# EchoReverbUnit.net
KiCad netlist of a schematic drawn in EAGLE
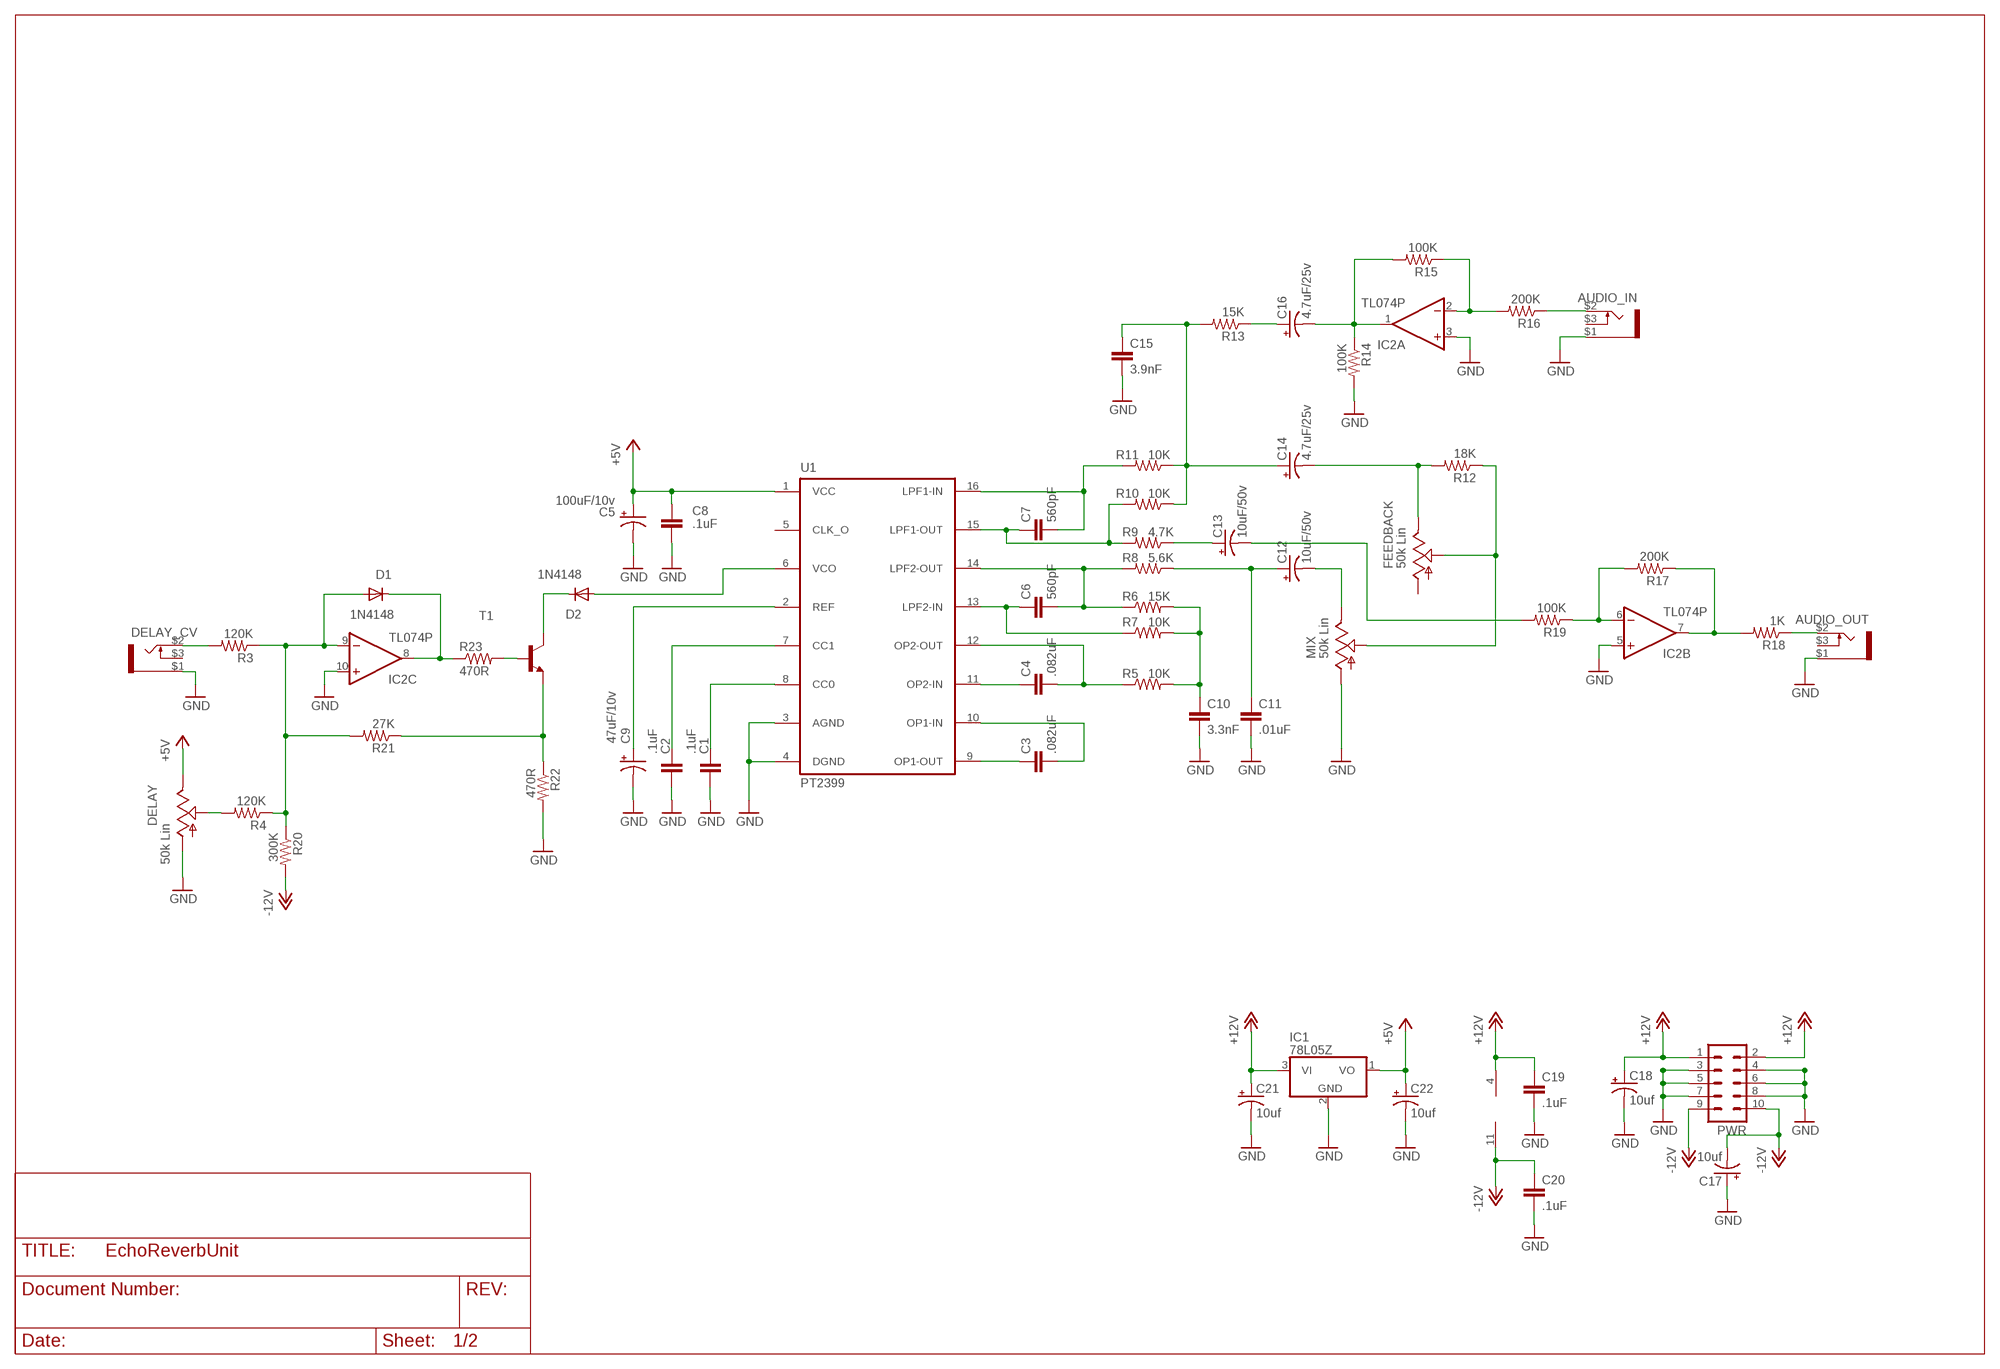
[diagram p0: schematic, sheet 1]

(export (version "E")
  (design (tool "Eeschema 10.0.6"))
  (components
    (comp (ref "AUDIO_IN")
      (value "PJ-323PJ-323")
      (footprint "eagle-import:PJ-323")
      (libsource (lib "eagle-import") (part "PJ-323PJ-323"))
    )
    (comp (ref "AUDIO_OUT")
      (value "PJ-323PJ-323")
      (footprint "eagle-import:PJ-323")
      (libsource (lib "eagle-import") (part "PJ-323PJ-323"))
    )
    (comp (ref "C1")
      (value ".1uF")
      (footprint "eagle-import:C050-024X044")
      (libsource (lib "eagle-import") (part "C-EU050-024X044"))
    )
    (comp (ref "C2")
      (value ".1uF")
      (footprint "eagle-import:C050-024X044")
      (libsource (lib "eagle-import") (part "C-EU050-024X044"))
    )
    (comp (ref "C3")
      (value ".082uF")
      (footprint "eagle-import:C050-024X044")
      (libsource (lib "eagle-import") (part "C-EU050-024X044"))
    )
    (comp (ref "C4")
      (value ".082uF")
      (footprint "eagle-import:C050-024X044")
      (libsource (lib "eagle-import") (part "C-EU050-024X044"))
    )
    (comp (ref "C5")
      (value "100uF/10v")
      (footprint "eagle-import:E2,5-6")
      (libsource (lib "eagle-import") (part "CPOL-USE2.5-6"))
    )
    (comp (ref "C6")
      (value "560pF")
      (footprint "eagle-import:C050-024X044")
      (libsource (lib "eagle-import") (part "C-EU050-024X044"))
    )
    (comp (ref "C7")
      (value "560pF")
      (footprint "eagle-import:C050-024X044")
      (libsource (lib "eagle-import") (part "C-EU050-024X044"))
    )
    (comp (ref "C8")
      (value ".1uF")
      (footprint "eagle-import:C050-024X044")
      (libsource (lib "eagle-import") (part "C-EU050-024X044"))
    )
    (comp (ref "C9")
      (value "47uF/10v")
      (footprint "eagle-import:E2,5-6")
      (libsource (lib "eagle-import") (part "CPOL-USE2.5-6"))
    )
    (comp (ref "C10")
      (value "3.3nF")
      (footprint "eagle-import:C050-024X044")
      (libsource (lib "eagle-import") (part "C-EU050-024X044"))
    )
    (comp (ref "C11")
      (value ".01uF")
      (footprint "eagle-import:C050-024X044")
      (libsource (lib "eagle-import") (part "C-EU050-024X044"))
    )
    (comp (ref "C12")
      (value "10uF/50v")
      (footprint "eagle-import:E2,5-6")
      (libsource (lib "eagle-import") (part "CPOL-USE2.5-6"))
    )
    (comp (ref "C13")
      (value "10uF/50v")
      (footprint "eagle-import:E2,5-6")
      (libsource (lib "eagle-import") (part "CPOL-USE2.5-6"))
    )
    (comp (ref "C14")
      (value "4.7uF/25v")
      (footprint "eagle-import:E2,5-6")
      (libsource (lib "eagle-import") (part "CPOL-USE2.5-6"))
    )
    (comp (ref "C15")
      (value "3.9nF")
      (footprint "eagle-import:C050-024X044")
      (libsource (lib "eagle-import") (part "C-EU050-024X044"))
    )
    (comp (ref "C16")
      (value "4.7uF/25v")
      (footprint "eagle-import:E2,5-6")
      (libsource (lib "eagle-import") (part "CPOL-USE2.5-6"))
    )
    (comp (ref "C17")
      (value "10uf")
      (footprint "eagle-import:E2,5-5")
      (libsource (lib "eagle-import") (part "CPOL-USE2.5-5"))
    )
    (comp (ref "C18")
      (value "10uf")
      (footprint "eagle-import:E2,5-5")
      (libsource (lib "eagle-import") (part "CPOL-USE2.5-5"))
    )
    (comp (ref "C19")
      (value ".1uF")
      (footprint "eagle-import:C050-024X044")
      (libsource (lib "eagle-import") (part "C-EU050-024X044"))
    )
    (comp (ref "C20")
      (value ".1uF")
      (footprint "eagle-import:C050-024X044")
      (libsource (lib "eagle-import") (part "C-EU050-024X044"))
    )
    (comp (ref "C21")
      (value "10uf")
      (footprint "eagle-import:E2,5-5")
      (libsource (lib "eagle-import") (part "CPOL-USE2.5-5"))
    )
    (comp (ref "C22")
      (value "10uf")
      (footprint "eagle-import:E2,5-5")
      (libsource (lib "eagle-import") (part "CPOL-USE2.5-5"))
    )
    (comp (ref "D1")
      (value "1N4148")
      (footprint "eagle-import:DO35-7")
      (libsource (lib "eagle-import") (part "1N4148DO35-7"))
    )
    (comp (ref "D2")
      (value "1N4148")
      (footprint "eagle-import:DO35-7")
      (libsource (lib "eagle-import") (part "1N4148DO35-7"))
    )
    (comp (ref "DELAY")
      (value "50k Lin")
      (footprint "eagle-import:EVUF")
      (libsource (lib "eagle-import") (part "RIGHT-ANGLE-POTA"))
    )
    (comp (ref "DELAY_CV")
      (value "PJ-323PJ-323")
      (footprint "eagle-import:PJ-323")
      (libsource (lib "eagle-import") (part "PJ-323PJ-323"))
    )
    (comp (ref "FEEDBACK")
      (value "50k Lin")
      (footprint "eagle-import:EVUF")
      (libsource (lib "eagle-import") (part "RIGHT-ANGLE-POTA"))
    )
    (comp (ref "IC1")
      (value "78L05Z")
      (footprint "eagle-import:TO92")
      (libsource (lib "eagle-import") (part "78ZL05"))
    )
    (comp (ref "IC2")
      (value "TL074P")
      (footprint "eagle-import:DIL14")
      (libsource (lib "eagle-import") (part "TL074P"))
    )
    (comp (ref "MIX")
      (value "50k Lin")
      (footprint "eagle-import:EVUF")
      (libsource (lib "eagle-import") (part "RIGHT-ANGLE-POTA"))
    )
    (comp (ref "PWR")
      (value "ML10")
      (footprint "eagle-import:ML10")
      (libsource (lib "eagle-import") (part "ML10"))
    )
    (comp (ref "R3")
      (value "120K")
      (footprint "eagle-import:0207_7")
      (libsource (lib "eagle-import") (part "R-US_0207/7"))
    )
    (comp (ref "R4")
      (value "120K")
      (footprint "eagle-import:0207_7")
      (libsource (lib "eagle-import") (part "R-US_0207/7"))
    )
    (comp (ref "R5")
      (value "10K")
      (footprint "eagle-import:0207_7")
      (libsource (lib "eagle-import") (part "R-US_0207/7"))
    )
    (comp (ref "R6")
      (value "15K")
      (footprint "eagle-import:0207_7")
      (libsource (lib "eagle-import") (part "R-US_0207/7"))
    )
    (comp (ref "R7")
      (value "10K")
      (footprint "eagle-import:0207_7")
      (libsource (lib "eagle-import") (part "R-US_0207/7"))
    )
    (comp (ref "R8")
      (value "5.6K")
      (footprint "eagle-import:0207_7")
      (libsource (lib "eagle-import") (part "R-US_0207/7"))
    )
    (comp (ref "R9")
      (value "4.7K")
      (footprint "eagle-import:0207_7")
      (libsource (lib "eagle-import") (part "R-US_0207/7"))
    )
    (comp (ref "R10")
      (value "10K")
      (footprint "eagle-import:0207_7")
      (libsource (lib "eagle-import") (part "R-US_0207/7"))
    )
    (comp (ref "R11")
      (value "10K")
      (footprint "eagle-import:0207_7")
      (libsource (lib "eagle-import") (part "R-US_0207/7"))
    )
    (comp (ref "R12")
      (value "18K")
      (footprint "eagle-import:0207_7")
      (libsource (lib "eagle-import") (part "R-US_0207/7"))
    )
    (comp (ref "R13")
      (value "15K")
      (footprint "eagle-import:0207_7")
      (libsource (lib "eagle-import") (part "R-US_0207/7"))
    )
    (comp (ref "R14")
      (value "100K")
      (footprint "eagle-import:0207_7")
      (libsource (lib "eagle-import") (part "R-US_0207/7"))
    )
    (comp (ref "R15")
      (value "100K")
      (footprint "eagle-import:0207_7")
      (libsource (lib "eagle-import") (part "R-US_0207/7"))
    )
    (comp (ref "R16")
      (value "200K")
      (footprint "eagle-import:0207_7")
      (libsource (lib "eagle-import") (part "R-US_0207/7"))
    )
    (comp (ref "R17")
      (value "200K")
      (footprint "eagle-import:0207_7")
      (libsource (lib "eagle-import") (part "R-US_0207/7"))
    )
    (comp (ref "R18")
      (value "1K")
      (footprint "eagle-import:0207_7")
      (libsource (lib "eagle-import") (part "R-US_0207/7"))
    )
    (comp (ref "R19")
      (value "100K")
      (footprint "eagle-import:0207_7")
      (libsource (lib "eagle-import") (part "R-US_0207/7"))
    )
    (comp (ref "R20")
      (value "300K")
      (footprint "eagle-import:0207_7")
      (libsource (lib "eagle-import") (part "R-US_0207/7"))
    )
    (comp (ref "R21")
      (value "27K")
      (footprint "eagle-import:0207_7")
      (libsource (lib "eagle-import") (part "R-US_0207/7"))
    )
    (comp (ref "R22")
      (value "470R")
      (footprint "eagle-import:0207_7")
      (libsource (lib "eagle-import") (part "R-US_0207/7"))
    )
    (comp (ref "R23")
      (value "470R")
      (footprint "eagle-import:0207_7")
      (libsource (lib "eagle-import") (part "R-US_0207/7"))
    )
    (comp (ref "T1")
      (value "2N3904-NPN-TO92-EBC")
      (footprint "eagle-import:TO92-EBC")
      (libsource (lib "eagle-import") (part "-NPN-TO92-EBC2N3904"))
    )
    (comp (ref "U1")
      (value "PT2399")
      (footprint "eagle-import:DIL16")
      (fields (field (name "MF") "AC Delco"))
      (libsource (lib "eagle-import") (part "PT2399"))
    )
  )
  (nets
    (net (code "1") (name "+5V") (class "Default")
      (node (ref "C22") (pin "+") (pinfunction "+_+") (pintype "passive"))
      (node (ref "C5") (pin "+") (pinfunction "+_+") (pintype "passive"))
      (node (ref "C8") (pin "1") (pinfunction "1_1") (pintype "passive"))
      (node (ref "DELAY") (pin "3") (pinfunction "E_3") (pintype "passive"))
      (node (ref "IC1") (pin "1") (pinfunction "VO_1") (pintype "passive"))
      (node (ref "U1") (pin "1") (pinfunction "VCC_1") (pintype "power_in"))
    )
    (net (code "2") (name "+12V") (class "Default")
      (node (ref "C18") (pin "+") (pinfunction "+_+") (pintype "passive"))
      (node (ref "C19") (pin "1") (pinfunction "1_1") (pintype "passive"))
      (node (ref "C21") (pin "+") (pinfunction "+_+") (pintype "passive"))
      (node (ref "IC1") (pin "3") (pinfunction "VI_3") (pintype "input"))
      (node (ref "IC2") (pin "4") (pinfunction "V+_4") (pintype "power_in"))
      (node (ref "PWR") (pin "1") (pinfunction "1_1") (pintype "passive"))
      (node (ref "PWR") (pin "2") (pinfunction "2_2") (pintype "passive"))
    )
    (net (code "3") (name "-12V") (class "Default")
      (node (ref "C17") (pin "-") (pinfunction "-_-") (pintype "passive"))
      (node (ref "C20") (pin "1") (pinfunction "1_1") (pintype "passive"))
      (node (ref "IC2") (pin "11") (pinfunction "V-_11") (pintype "power_in"))
      (node (ref "PWR") (pin "10") (pinfunction "10_10") (pintype "passive"))
      (node (ref "PWR") (pin "9") (pinfunction "9_9") (pintype "passive"))
      (node (ref "R20") (pin "2") (pinfunction "2_2") (pintype "passive"))
    )
    (net (code "4") (name "GND") (class "Default")
      (node (ref "AUDIO_IN") (pin "$1") (pinfunction "3_$1") (pintype "passive"))
      (node (ref "AUDIO_OUT") (pin "$1") (pinfunction "3_$1") (pintype "passive"))
      (node (ref "C1") (pin "2") (pinfunction "2_2") (pintype "passive"))
      (node (ref "C10") (pin "2") (pinfunction "2_2") (pintype "passive"))
      (node (ref "C11") (pin "2") (pinfunction "2_2") (pintype "passive"))
      (node (ref "C15") (pin "2") (pinfunction "2_2") (pintype "passive"))
      (node (ref "C17") (pin "+") (pinfunction "+_+") (pintype "passive"))
      (node (ref "C18") (pin "-") (pinfunction "-_-") (pintype "passive"))
      (node (ref "C19") (pin "2") (pinfunction "2_2") (pintype "passive"))
      (node (ref "C2") (pin "2") (pinfunction "2_2") (pintype "passive"))
      (node (ref "C20") (pin "2") (pinfunction "2_2") (pintype "passive"))
      (node (ref "C21") (pin "-") (pinfunction "-_-") (pintype "passive"))
      (node (ref "C22") (pin "-") (pinfunction "-_-") (pintype "passive"))
      (node (ref "C5") (pin "-") (pinfunction "-_-") (pintype "passive"))
      (node (ref "C8") (pin "2") (pinfunction "2_2") (pintype "passive"))
      (node (ref "C9") (pin "-") (pinfunction "-_-") (pintype "passive"))
      (node (ref "DELAY") (pin "1") (pinfunction "A_1") (pintype "passive"))
      (node (ref "DELAY_CV") (pin "$1") (pinfunction "3_$1") (pintype "passive"))
      (node (ref "IC1") (pin "2") (pinfunction "GND_2") (pintype "passive"))
      (node (ref "IC2") (pin "10") (pinfunction "+IN_10") (pintype "input"))
      (node (ref "IC2") (pin "3") (pinfunction "+IN_3") (pintype "input"))
      (node (ref "IC2") (pin "5") (pinfunction "+IN_5") (pintype "input"))
      (node (ref "MIX") (pin "1") (pinfunction "A_1") (pintype "passive"))
      (node (ref "PWR") (pin "3") (pinfunction "3_3") (pintype "passive"))
      (node (ref "PWR") (pin "4") (pinfunction "4_4") (pintype "passive"))
      (node (ref "PWR") (pin "5") (pinfunction "5_5") (pintype "passive"))
      (node (ref "PWR") (pin "6") (pinfunction "6_6") (pintype "passive"))
      (node (ref "PWR") (pin "7") (pinfunction "7_7") (pintype "passive"))
      (node (ref "PWR") (pin "8") (pinfunction "8_8") (pintype "passive"))
      (node (ref "R14") (pin "2") (pinfunction "2_2") (pintype "passive"))
      (node (ref "R22") (pin "2") (pinfunction "2_2") (pintype "passive"))
      (node (ref "U1") (pin "3") (pinfunction "AGND_3") (pintype "power_in"))
      (node (ref "U1") (pin "4") (pinfunction "DGND_4") (pintype "power_in"))
    )
    (net (code "5") (name "Net-(AUDIO_IN-1)") (class "Default")
      (node (ref "AUDIO_IN") (pin "$2") (pinfunction "1_$2") (pintype "passive"))
      (node (ref "R16") (pin "1") (pinfunction "1_1") (pintype "passive"))
    )
    (net (code "6") (name "Net-(AUDIO_OUT-1)") (class "Default")
      (node (ref "AUDIO_OUT") (pin "$2") (pinfunction "1_$2") (pintype "passive"))
      (node (ref "R18") (pin "1") (pinfunction "1_1") (pintype "passive"))
    )
    (net (code "7") (name "Net-(C10-Pad1)") (class "Default")
      (node (ref "C10") (pin "1") (pinfunction "1_1") (pintype "passive"))
      (node (ref "R5") (pin "2") (pinfunction "2_2") (pintype "passive"))
      (node (ref "R6") (pin "2") (pinfunction "2_2") (pintype "passive"))
      (node (ref "R7") (pin "2") (pinfunction "2_2") (pintype "passive"))
    )
    (net (code "8") (name "Net-(C11-Pad1)") (class "Default")
      (node (ref "C11") (pin "1") (pinfunction "1_1") (pintype "passive"))
      (node (ref "C12") (pin "+") (pinfunction "+_+") (pintype "passive"))
      (node (ref "R8") (pin "1") (pinfunction "1_1") (pintype "passive"))
    )
    (net (code "9") (name "Net-(C13-Pad+)") (class "Default")
      (node (ref "C13") (pin "+") (pinfunction "+_+") (pintype "passive"))
      (node (ref "R9") (pin "1") (pinfunction "1_1") (pintype "passive"))
    )
    (net (code "10") (name "Net-(C13-Pad-)") (class "Default")
      (node (ref "C13") (pin "-") (pinfunction "-_-") (pintype "passive"))
      (node (ref "R19") (pin "2") (pinfunction "2_2") (pintype "passive"))
    )
    (net (code "11") (name "Net-(C14-Pad+)") (class "Default")
      (node (ref "C14") (pin "+") (pinfunction "+_+") (pintype "passive"))
      (node (ref "C15") (pin "1") (pinfunction "1_1") (pintype "passive"))
      (node (ref "R10") (pin "1") (pinfunction "1_1") (pintype "passive"))
      (node (ref "R11") (pin "1") (pinfunction "1_1") (pintype "passive"))
      (node (ref "R13") (pin "2") (pinfunction "2_2") (pintype "passive"))
    )
    (net (code "12") (name "Net-(C16-Pad+)") (class "Default")
      (node (ref "C16") (pin "+") (pinfunction "+_+") (pintype "passive"))
      (node (ref "R13") (pin "1") (pinfunction "1_1") (pintype "passive"))
    )
    (net (code "13") (name "Net-(D2-PadC)") (class "Default")
      (node (ref "D2") (pin "C") (pinfunction "C_C") (pintype "passive"))
      (node (ref "T1") (pin "C") (pinfunction "C_C") (pintype "passive"))
    )
    (net (code "14") (name "Net-(DELAY-S)") (class "Default")
      (node (ref "DELAY") (pin "2") (pinfunction "S_2") (pintype "passive"))
      (node (ref "R4") (pin "2") (pinfunction "2_2") (pintype "passive"))
    )
    (net (code "15") (name "Net-(DELAY_CV-1)") (class "Default")
      (node (ref "DELAY_CV") (pin "$2") (pinfunction "1_$2") (pintype "passive"))
      (node (ref "R3") (pin "2") (pinfunction "2_2") (pintype "passive"))
    )
    (net (code "16") (name "Net-(FEEDBACK-E)") (class "Default")
      (node (ref "C14") (pin "-") (pinfunction "-_-") (pintype "passive"))
      (node (ref "FEEDBACK") (pin "3") (pinfunction "E_3") (pintype "passive"))
      (node (ref "R12") (pin "2") (pinfunction "2_2") (pintype "passive"))
    )
    (net (code "17") (name "Net-(FEEDBACK-S)") (class "Default")
      (node (ref "FEEDBACK") (pin "2") (pinfunction "S_2") (pintype "passive"))
      (node (ref "MIX") (pin "2") (pinfunction "S_2") (pintype "passive"))
      (node (ref "R12") (pin "1") (pinfunction "1_1") (pintype "passive"))
    )
    (net (code "18") (name "Net-(IC2A--IN)") (class "Default")
      (node (ref "IC2") (pin "2") (pinfunction "-IN_2") (pintype "input"))
      (node (ref "R15") (pin "1") (pinfunction "1_1") (pintype "passive"))
      (node (ref "R16") (pin "2") (pinfunction "2_2") (pintype "passive"))
    )
    (net (code "19") (name "Net-(IC2A-OUT)") (class "Default")
      (node (ref "C16") (pin "-") (pinfunction "-_-") (pintype "passive"))
      (node (ref "IC2") (pin "1") (pinfunction "OUT_1") (pintype "output"))
      (node (ref "R14") (pin "1") (pinfunction "1_1") (pintype "passive"))
      (node (ref "R15") (pin "2") (pinfunction "2_2") (pintype "passive"))
    )
    (net (code "20") (name "Net-(IC2B--IN)") (class "Default")
      (node (ref "IC2") (pin "6") (pinfunction "-IN_6") (pintype "input"))
      (node (ref "R17") (pin "2") (pinfunction "2_2") (pintype "passive"))
      (node (ref "R19") (pin "1") (pinfunction "1_1") (pintype "passive"))
    )
    (net (code "21") (name "Net-(IC2B-OUT)") (class "Default")
      (node (ref "IC2") (pin "7") (pinfunction "OUT_7") (pintype "output"))
      (node (ref "R17") (pin "1") (pinfunction "1_1") (pintype "passive"))
      (node (ref "R18") (pin "2") (pinfunction "2_2") (pintype "passive"))
    )
    (net (code "22") (name "Net-(IC2C--IN)") (class "Default")
      (node (ref "D1") (pin "A") (pinfunction "A_A") (pintype "passive"))
      (node (ref "IC2") (pin "9") (pinfunction "-IN_9") (pintype "input"))
      (node (ref "R20") (pin "1") (pinfunction "1_1") (pintype "passive"))
      (node (ref "R21") (pin "2") (pinfunction "2_2") (pintype "passive"))
      (node (ref "R3") (pin "1") (pinfunction "1_1") (pintype "passive"))
      (node (ref "R4") (pin "1") (pinfunction "1_1") (pintype "passive"))
    )
    (net (code "23") (name "Net-(IC2C-OUT)") (class "Default")
      (node (ref "D1") (pin "C") (pinfunction "C_C") (pintype "passive"))
      (node (ref "IC2") (pin "8") (pinfunction "OUT_8") (pintype "output"))
      (node (ref "R23") (pin "1") (pinfunction "1_1") (pintype "passive"))
    )
    (net (code "24") (name "Net-(MIX-E)") (class "Default")
      (node (ref "C12") (pin "-") (pinfunction "-_-") (pintype "passive"))
      (node (ref "MIX") (pin "3") (pinfunction "E_3") (pintype "passive"))
    )
    (net (code "25") (name "Net-(R21-Pad1)") (class "Default")
      (node (ref "R21") (pin "1") (pinfunction "1_1") (pintype "passive"))
      (node (ref "R22") (pin "1") (pinfunction "1_1") (pintype "passive"))
      (node (ref "T1") (pin "E") (pinfunction "E_E") (pintype "passive"))
    )
    (net (code "26") (name "Net-(R23-Pad2)") (class "Default")
      (node (ref "R23") (pin "2") (pinfunction "2_2") (pintype "passive"))
      (node (ref "T1") (pin "B") (pinfunction "B_B") (pintype "passive"))
    )
    (net (code "27") (name "Net-(U1-CC0)") (class "Default")
      (node (ref "C1") (pin "1") (pinfunction "1_1") (pintype "passive"))
      (node (ref "U1") (pin "8") (pinfunction "CC0_8") (pintype "input"))
    )
    (net (code "28") (name "Net-(U1-CC1)") (class "Default")
      (node (ref "C2") (pin "1") (pinfunction "1_1") (pintype "passive"))
      (node (ref "U1") (pin "7") (pinfunction "CC1_7") (pintype "input"))
    )
    (net (code "29") (name "Net-(U1-LPF1-IN)") (class "Default")
      (node (ref "C7") (pin "2") (pinfunction "2_2") (pintype "passive"))
      (node (ref "R11") (pin "2") (pinfunction "2_2") (pintype "passive"))
      (node (ref "U1") (pin "16") (pinfunction "LPF1-IN_16") (pintype "input"))
    )
    (net (code "30") (name "Net-(U1-LPF1-OUT)") (class "Default")
      (node (ref "C7") (pin "1") (pinfunction "1_1") (pintype "passive"))
      (node (ref "R10") (pin "2") (pinfunction "2_2") (pintype "passive"))
      (node (ref "R9") (pin "2") (pinfunction "2_2") (pintype "passive"))
      (node (ref "U1") (pin "15") (pinfunction "LPF1-OUT_15") (pintype "output"))
    )
    (net (code "31") (name "Net-(U1-LPF2-IN)") (class "Default")
      (node (ref "C6") (pin "1") (pinfunction "1_1") (pintype "passive"))
      (node (ref "R7") (pin "1") (pinfunction "1_1") (pintype "passive"))
      (node (ref "U1") (pin "13") (pinfunction "LPF2-IN_13") (pintype "input"))
    )
    (net (code "32") (name "Net-(U1-LPF2-OUT)") (class "Default")
      (node (ref "C6") (pin "2") (pinfunction "2_2") (pintype "passive"))
      (node (ref "R6") (pin "1") (pinfunction "1_1") (pintype "passive"))
      (node (ref "R8") (pin "2") (pinfunction "2_2") (pintype "passive"))
      (node (ref "U1") (pin "14") (pinfunction "LPF2-OUT_14") (pintype "output"))
    )
    (net (code "33") (name "Net-(U1-OP1-IN)") (class "Default")
      (node (ref "C3") (pin "2") (pinfunction "2_2") (pintype "passive"))
      (node (ref "U1") (pin "10") (pinfunction "OP1-IN_10") (pintype "input"))
    )
    (net (code "34") (name "Net-(U1-OP1-OUT)") (class "Default")
      (node (ref "C3") (pin "1") (pinfunction "1_1") (pintype "passive"))
      (node (ref "U1") (pin "9") (pinfunction "OP1-OUT_9") (pintype "output"))
    )
    (net (code "35") (name "Net-(U1-OP2-IN)") (class "Default")
      (node (ref "C4") (pin "1") (pinfunction "1_1") (pintype "passive"))
      (node (ref "U1") (pin "11") (pinfunction "OP2-IN_11") (pintype "input"))
    )
    (net (code "36") (name "Net-(U1-OP2-OUT)") (class "Default")
      (node (ref "C4") (pin "2") (pinfunction "2_2") (pintype "passive"))
      (node (ref "R5") (pin "1") (pinfunction "1_1") (pintype "passive"))
      (node (ref "U1") (pin "12") (pinfunction "OP2-OUT_12") (pintype "output"))
    )
    (net (code "37") (name "Net-(U1-REF)") (class "Default")
      (node (ref "C9") (pin "+") (pinfunction "+_+") (pintype "passive"))
      (node (ref "U1") (pin "2") (pinfunction "REF_2") (pintype "input"))
    )
    (net (code "38") (name "Net-(U1-VCO)") (class "Default")
      (node (ref "D2") (pin "A") (pinfunction "A_A") (pintype "passive"))
      (node (ref "U1") (pin "6") (pinfunction "VCO_6") (pintype "input"))
    )
    (net (code "39") (name "unconnected-(AUDIO_IN-2-Pad$3)") (class "Default")
      (node (ref "AUDIO_IN") (pin "$3") (pinfunction "2_$3") (pintype "passive"))
    )
    (net (code "40") (name "unconnected-(AUDIO_OUT-2-Pad$3)") (class "Default")
      (node (ref "AUDIO_OUT") (pin "$3") (pinfunction "2_$3") (pintype "passive"))
    )
    (net (code "41") (name "unconnected-(DELAY_CV-2-Pad$3)") (class "Default")
      (node (ref "DELAY_CV") (pin "$3") (pinfunction "2_$3") (pintype "passive"))
    )
    (net (code "42") (name "unconnected-(FEEDBACK-A-Pad1)") (class "Default")
      (node (ref "FEEDBACK") (pin "1") (pinfunction "A_1") (pintype "passive"))
    )
    (net (code "43") (name "unconnected-(U1-CLK_O-Pad5)") (class "Default")
      (node (ref "U1") (pin "5") (pinfunction "CLK_O_5") (pintype "output"))
    )
  )
)
